# v1-3b.net
KiCad netlist of a schematic drawn in Altium Designer
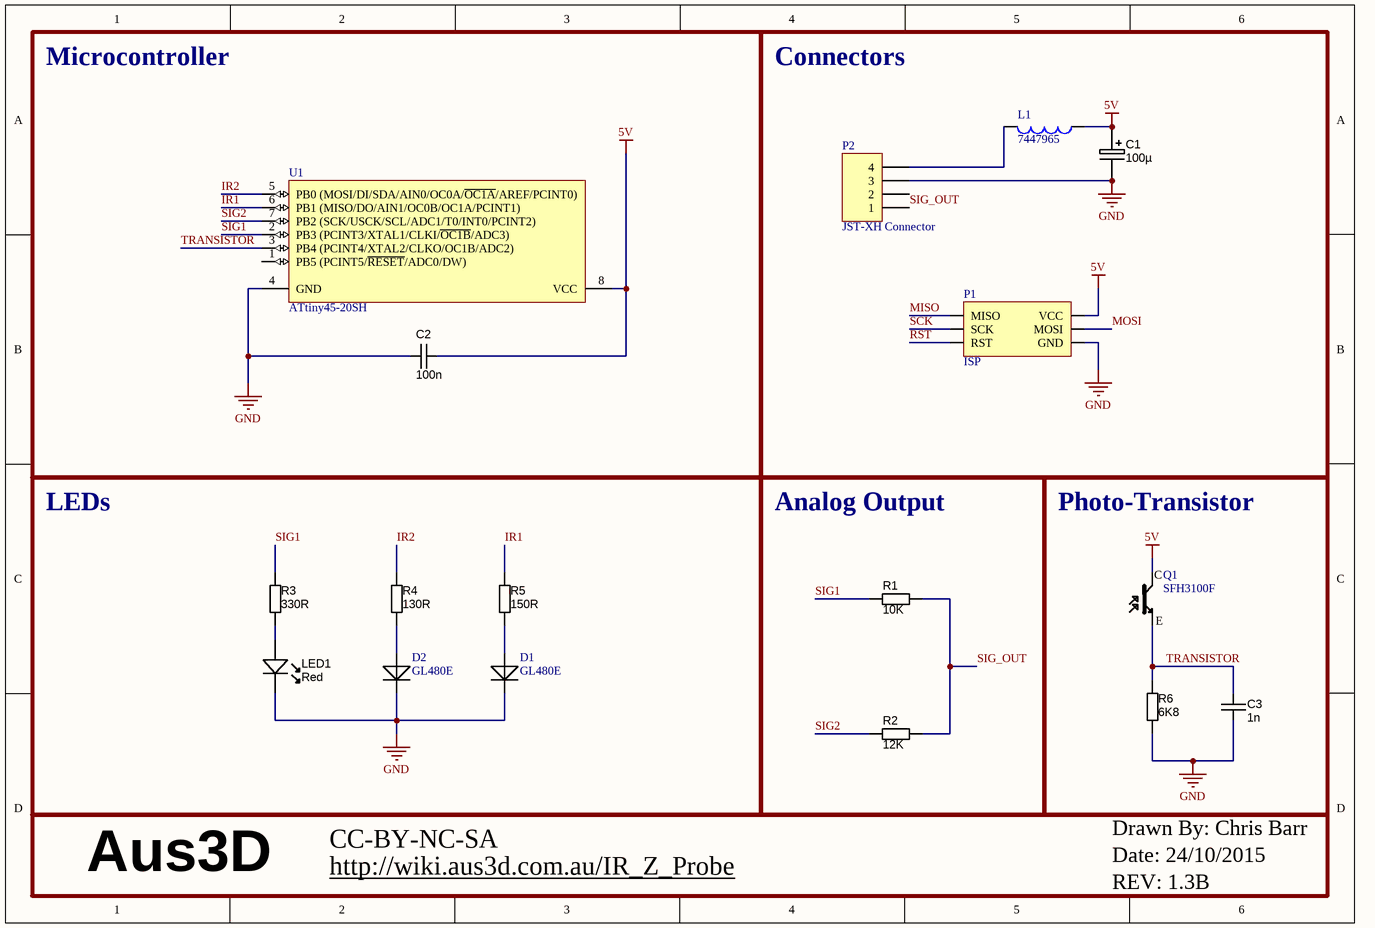
[diagram p0: v1-3b.SchDoc]

(export (version "E")
  (design (tool "Eeschema 10.0.6"))
  (components
    (comp (ref "C1")
      (value "100µ")
      (footprint "6.3-DIA-CAP")
      (description "Capacitor THD Electrolytic 100uF 20% 16V Radial")
      (fields (field (name "TOLERANCE") "±20%") (field (name "MANUFACTURER") "Panasonic - ECG"))
      (libsource (lib "PBL - Capacitors") (part "CAPE_100u_16V_THD"))
    )
    (comp (ref "C2")
      (value "100n")
      (footprint "CAPC1005X55N")
      (description "Capacitor SMD Cer 100nF 10% 16V X5R 0402")
      (fields (field (name "TOLERANCE") "±10%"))
      (libsource (lib "PBL - Capacitors") (part "CAPC_100n_0402_X5R_16V_10%"))
    )
    (comp (ref "C3")
      (value "1n")
      (footprint "CAPC1005X55N")
      (description "Capacitor SMD Cer 1nF 10% 16V X7R 0402")
      (fields (field (name "TOLERANCE") "±10%"))
      (libsource (lib "PBL - Capacitors") (part "CAPC_1n_0402_X7R_16V_10%"))
    )
    (comp (ref "D1")
      (value "GL480E")
      (footprint "LED-2.54spacing")
      (libsource (lib "Schlib1") (part "GL480E"))
    )
    (comp (ref "D2")
      (value "GL480E")
      (footprint "LED-2.54spacing")
      (libsource (lib "Schlib1") (part "GL480E"))
    )
    (comp (ref "L1")
      (value "7447965")
      (footprint "SMD-0603")
      (description "SMD-Multilayer Inductor WE-MI, L = 1.00 µH")
      (libsource (lib "Wuerth Elektronik Filter Inductor") (part "7447965"))
    )
    (comp (ref "LED1")
      (value "Red")
      (footprint "LED-0603-RED")
      (description "LED 0603 SMD Hyper Red 630nm 220mcd 20mA")
      (libsource (lib "PBL - Light Sources") (part "LED_SMD_Red_0603_220mcd"))
    )
    (comp (ref "P1") (value "ISP") (footprint "ICSP Pads") (libsource (lib "Schlib1") (part "ISP Header")))
    (comp (ref "P2")
      (value "JST-XH Connector")
      (footprint "JST-4P")
      (description "Header, 4-Pin")
      (fields (field (name "PUBLISHER") "Altium Limited"))
      (libsource (lib "Miscellaneous Connectors") (part "Header 4"))
    )
    (comp (ref "Q1")
      (value "SFH3100F")
      (footprint "SFH3100F-footprint")
      (description "GL480E")
      (libsource (lib "Schlib1") (part "SFH3100F"))
    )
    (comp (ref "R1")
      (value "10K")
      (footprint "RESC1608X55N")
      (description "Resistor SMD chip 2.2k Ohm 0.1W 5% 0603")
      (fields (field (name "TOLERANCE") "±5%") (field (name "Comment") "Thick Film"))
      (libsource (lib "") (part "RES_2K2_0603_5%_1"))
    )
    (comp (ref "R2")
      (value "12K")
      (footprint "RESC1608X55N")
      (description "Resistor SMD chip 2.2k Ohm 0.1W 5% 0603")
      (fields (field (name "TOLERANCE") "±5%") (field (name "Comment") "Thick Film"))
      (libsource (lib "") (part "RES_2K2_0603_5%_1"))
    )
    (comp (ref "R3")
      (value "330R")
      (footprint "RESC1608X55N")
      (description "Resistor SMD chip 330 Ohm 0.1W 5% 0603")
      (fields (field (name "TOLERANCE") "±5%") (field (name "Comment") "Thick Film"))
      (libsource (lib "PBL - Resistors") (part "RES_330R_0603_5%"))
    )
    (comp (ref "R4")
      (value "130R")
      (footprint "RESC1608X55N")
      (description "Resistor SMD chip 2.2k Ohm 0.1W 5% 0603")
      (fields (field (name "TOLERANCE") "±5%") (field (name "Comment") "Thick Film"))
      (libsource (lib "PBL - Resistors") (part "RES_2K2_0603_5%"))
    )
    (comp (ref "R5")
      (value "150R")
      (footprint "RESC1608X55N")
      (description "Resistor SMD chip 2.2k Ohm 0.1W 5% 0603")
      (fields (field (name "TOLERANCE") "±5%") (field (name "Comment") "Thick Film"))
      (libsource (lib "PBL - Resistors") (part "RES_2K2_0603_5%"))
    )
    (comp (ref "R6")
      (value "6K8")
      (footprint "RESC1608X55N")
      (description "Resistor SMD chip 2.2k Ohm 0.1W 5% 0603")
      (fields (field (name "TOLERANCE") "±5%") (field (name "Comment") "Thick Film"))
      (libsource (lib "PBL - Resistors") (part "RES_2K2_0603_5%"))
    )
    (comp (ref "U1")
      (value "ATtiny45-20SH")
      (footprint "8S2_N")
      (libsource (lib "Atmel Microcontroller tinyAVR") (part "ATtiny45-20SH"))
    )
  )
  (nets
    (net (code "1") (name "/IR1") (class "Default")
      (node (ref "R5") (pin "2") (pinfunction "2_2") (pintype "passive"))
      (node (ref "U1") (pin "6") (pinfunction "PB1_(MISO/DO/AIN1/OC0B/OC1A/PCINT1)_6") (pintype "bidirectional"))
    )
    (net (code "2") (name "/IR2") (class "Default")
      (node (ref "R4") (pin "2") (pinfunction "2_2") (pintype "passive"))
      (node (ref "U1") (pin "5") (pinfunction "PB0_(MOSI/DI/SDA/AIN0/OC0A/~{OC1A}/AREF/PCINT0)_5") (pintype "bidirectional"))
    )
    (net (code "3") (name "/MISO") (class "Default")
      (node (ref "P1") (pin "0") (pinfunction "MISO_0") (pintype "passive"))
    )
    (net (code "4") (name "/MOSI") (class "Default")
      (node (ref "P1") (pin "3") (pinfunction "MOSI_3") (pintype "passive"))
    )
    (net (code "5") (name "/RST") (class "Default")
      (node (ref "P1") (pin "4") (pinfunction "RST_4") (pintype "passive"))
    )
    (net (code "6") (name "/SCK") (class "Default")
      (node (ref "P1") (pin "2") (pinfunction "SCK_2") (pintype "passive"))
    )
    (net (code "7") (name "/SIG1") (class "Default")
      (node (ref "R1") (pin "2") (pinfunction "2_2") (pintype "passive"))
      (node (ref "R3") (pin "1") (pinfunction "1_1") (pintype "passive"))
      (node (ref "U1") (pin "2") (pinfunction "PB3_(PCINT3/XTAL1/CLKI/~{OC1B}/ADC3)_2") (pintype "bidirectional"))
    )
    (net (code "8") (name "/SIG2") (class "Default")
      (node (ref "R2") (pin "2") (pinfunction "2_2") (pintype "passive"))
      (node (ref "U1") (pin "7") (pinfunction "PB2_(SCK/USCK/SCL/ADC1/T0/INT0/PCINT2)_7") (pintype "bidirectional"))
    )
    (net (code "9") (name "/SIG_OUT") (class "Default")
      (node (ref "P2") (pin "1") (pinfunction "1_1") (pintype "passive"))
      (node (ref "R1") (pin "1") (pinfunction "1_1") (pintype "passive"))
      (node (ref "R2") (pin "1") (pinfunction "1_1") (pintype "passive"))
    )
    (net (code "10") (name "/TRANSISTOR") (class "Default")
      (node (ref "C3") (pin "1") (pintype "passive"))
      (node (ref "Q1") (pin "2") (pinfunction "2_2") (pintype "passive"))
      (node (ref "R6") (pin "2") (pinfunction "2_2") (pintype "passive"))
      (node (ref "U1") (pin "3") (pinfunction "PB4_(PCINT4/XTAL2/CLKO/OC1B/ADC2)_3") (pintype "bidirectional"))
    )
    (net (code "11") (name "5V") (class "Default")
      (node (ref "C1") (pin "1") (pintype "passive"))
      (node (ref "C2") (pin "2") (pintype "passive"))
      (node (ref "L1") (pin "1") (pinfunction "1_1") (pintype "passive"))
      (node (ref "P1") (pin "1") (pinfunction "VCC_1") (pintype "passive"))
      (node (ref "Q1") (pin "1") (pinfunction "1_1") (pintype "passive"))
      (node (ref "U1") (pin "8") (pinfunction "VCC_8") (pintype "power_in"))
    )
    (net (code "12") (name "GND") (class "Default")
      (node (ref "C1") (pin "2") (pintype "passive"))
      (node (ref "C2") (pin "1") (pintype "passive"))
      (node (ref "C3") (pin "2") (pintype "passive"))
      (node (ref "D1") (pin "1") (pinfunction "1_1") (pintype "passive"))
      (node (ref "D2") (pin "1") (pinfunction "1_1") (pintype "passive"))
      (node (ref "LED1") (pin "K") (pinfunction "K_K") (pintype "passive"))
      (node (ref "P1") (pin "5") (pinfunction "GND_5") (pintype "passive"))
      (node (ref "P2") (pin "3") (pinfunction "3_3") (pintype "passive"))
      (node (ref "R6") (pin "1") (pinfunction "1_1") (pintype "passive"))
      (node (ref "U1") (pin "4") (pinfunction "GND_4") (pintype "power_in"))
    )
    (net (code "13") (name "Net-(D1-Pad2)") (class "Default")
      (node (ref "D1") (pin "2") (pinfunction "2_2") (pintype "passive"))
      (node (ref "R5") (pin "1") (pinfunction "1_1") (pintype "passive"))
    )
    (net (code "14") (name "Net-(D2-Pad2)") (class "Default")
      (node (ref "D2") (pin "2") (pinfunction "2_2") (pintype "passive"))
      (node (ref "R4") (pin "1") (pinfunction "1_1") (pintype "passive"))
    )
    (net (code "15") (name "Net-(L1-Pad2)") (class "Default")
      (node (ref "L1") (pin "2") (pinfunction "2_2") (pintype "passive"))
      (node (ref "P2") (pin "4") (pinfunction "4_4") (pintype "passive"))
    )
    (net (code "16") (name "Net-(LED1-PadA)") (class "Default")
      (node (ref "LED1") (pin "A") (pinfunction "A_A") (pintype "passive"))
      (node (ref "R3") (pin "2") (pinfunction "2_2") (pintype "passive"))
    )
    (net (code "17") (name "unconnected-(P2-Pad2)") (class "Default")
      (node (ref "P2") (pin "2") (pinfunction "2_2") (pintype "passive"))
    )
    (net (code "18") (name "unconnected-(U1-PB5_(PCINT5{slash}~{RESET}{slash}ADC0{slash}DW)-Pad1)") (class "Default")
      (node (ref "U1") (pin "1") (pinfunction "PB5_(PCINT5/~{RESET}/ADC0/DW)_1") (pintype "bidirectional"))
    )
  )
)
